# SCH_PCBproject_2024-10-10.net
KiCad netlist of a schematic drawn in EasyEDA
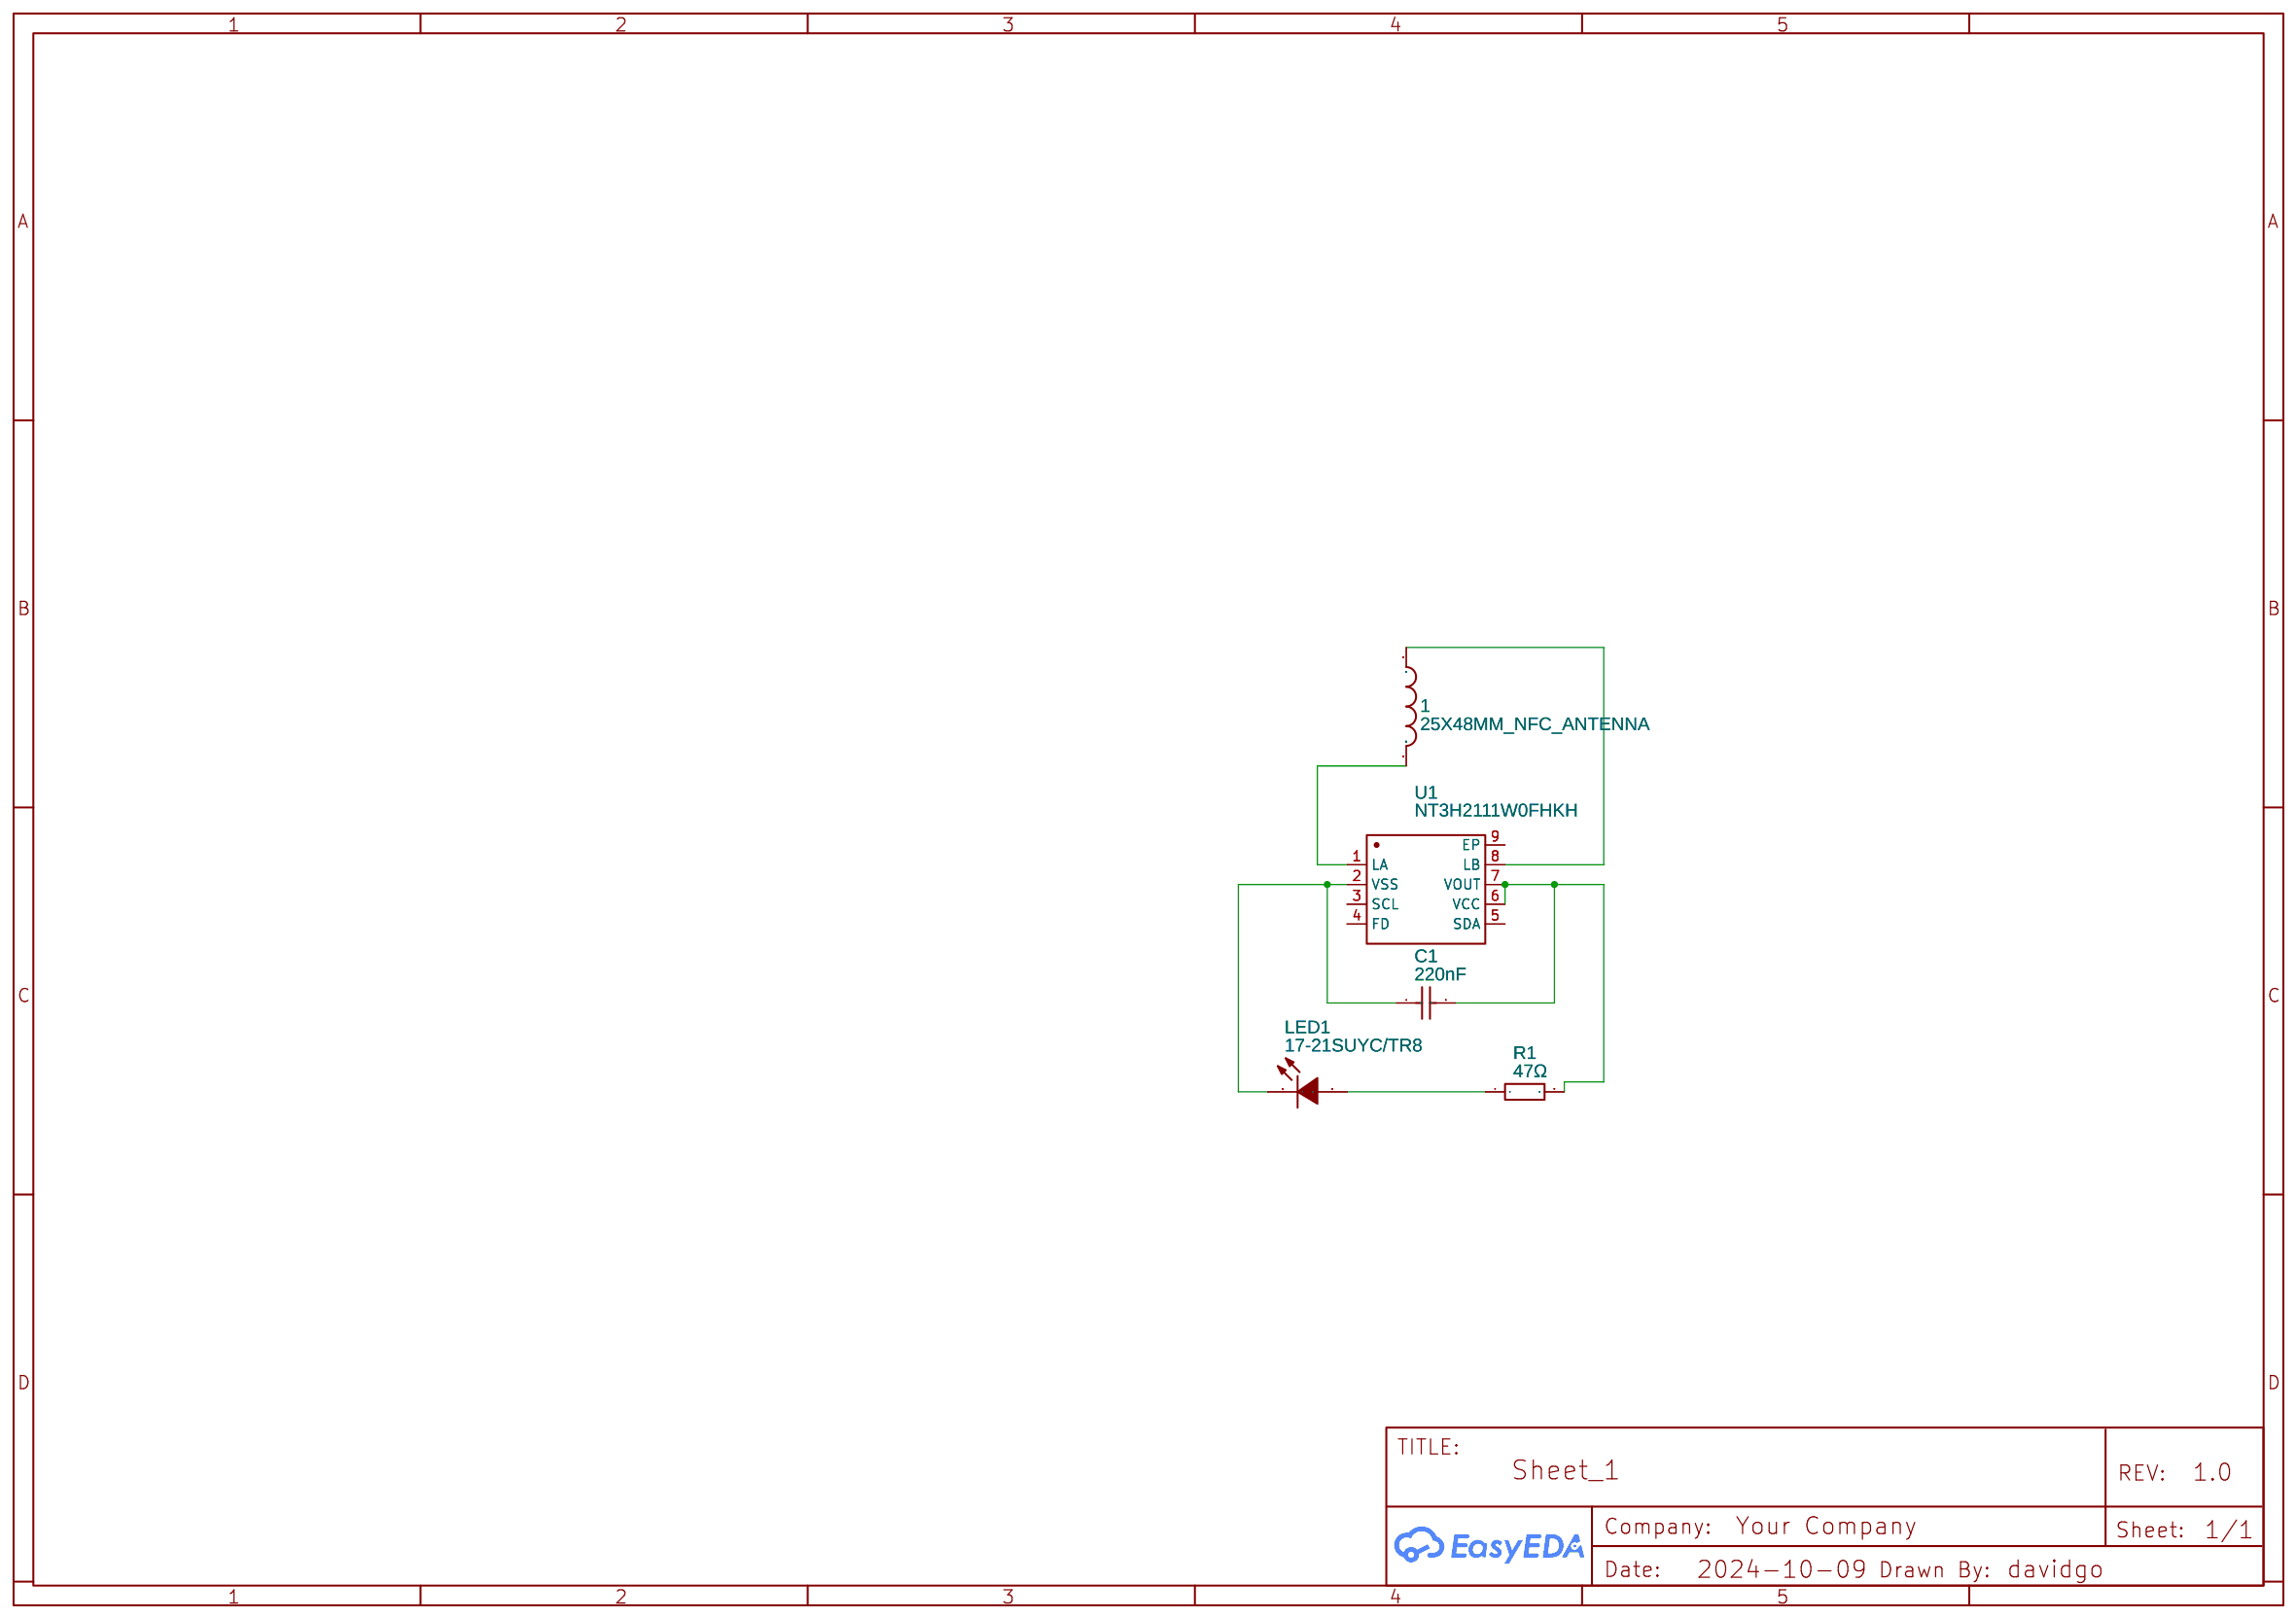
[diagram p0: schematic sheet]

(export (version "E")
  (design (tool "Eeschema 10.0.6"))
  (components
    (comp (ref "1") (value "25X48MM_NFC_ANTENNA") (libsource (lib "") (part "25X48MM_NFC_ANTENNA")))
    (comp (ref "C1")
      (value "220nF")
      (fields
        (field (name "Manufacturer Part") "CL10B224KA8NNNC")
        (field (name "Manufacturer") "SAMSUNG(三星)")
      )
      (libsource (lib "") (part "CL10B224KA8NNNC"))
    )
    (comp (ref "LED1")
      (value "17-21SUYC/TR8")
      (fields (field (name "Manufacturer Part") "KT-0805黄灯") (field (name "Manufacturer") "KENTO"))
      (libsource (lib "") (part "17-21SUYC/TR8"))
    )
    (comp (ref "R1")
      (value "47Ω")
      (fields
        (field (name "Manufacturer Part") "0603WAF470JT5E")
        (field (name "Manufacturer") "UNI-ROYAL(厚声)")
      )
      (libsource (lib "") (part "0603WAF470JT5E"))
    )
    (comp (ref "U1")
      (value "NT3H2111W0FHKH")
      (fields (field (name "Manufacturer") "NXP(恩智浦)"))
      (libsource (lib "") (part "NT3H2111W0FHKH"))
    )
  )
  (nets
    (net (code "1") (name "Net-(LED1-+)") (class "Default")
      (node (ref "LED1") (pin "1") (pinfunction "+_1") (pintype "unspecified"))
      (node (ref "R1") (pin "1") (pinfunction "1_1") (pintype "input"))
    )
    (net (code "2") (name "Net-(LED1--)") (class "Default")
      (node (ref "C1") (pin "1") (pinfunction "1_1") (pintype "input"))
      (node (ref "LED1") (pin "2") (pinfunction "-_2") (pintype "unspecified"))
      (node (ref "U1") (pin "2") (pinfunction "VSS_2") (pintype "unspecified"))
    )
    (net (code "3") (name "Net-(U1-LA)") (class "Default")
      (node (ref "1") (pin "P$2") (pinfunction "P$2_P$2") (pintype "bidirectional"))
      (node (ref "U1") (pin "1") (pinfunction "LA_1") (pintype "unspecified"))
    )
    (net (code "4") (name "Net-(U1-LB)") (class "Default")
      (node (ref "1") (pin "P$1") (pinfunction "P$1_P$1") (pintype "bidirectional"))
      (node (ref "U1") (pin "8") (pinfunction "LB_8") (pintype "unspecified"))
    )
    (net (code "5") (name "Net-(U1-VCC)") (class "Default")
      (node (ref "C1") (pin "2") (pinfunction "2_2") (pintype "input"))
      (node (ref "R1") (pin "2") (pinfunction "2_2") (pintype "input"))
      (node (ref "U1") (pin "6") (pinfunction "VCC_6") (pintype "unspecified"))
      (node (ref "U1") (pin "7") (pinfunction "VOUT_7") (pintype "unspecified"))
    )
    (net (code "6") (name "unconnected-(U1-EP-Pad9)") (class "Default")
      (node (ref "U1") (pin "9") (pinfunction "EP_9") (pintype "unspecified"))
    )
    (net (code "7") (name "unconnected-(U1-FD-Pad4)") (class "Default")
      (node (ref "U1") (pin "4") (pinfunction "FD_4") (pintype "unspecified"))
    )
    (net (code "8") (name "unconnected-(U1-SCL-Pad3)") (class "Default")
      (node (ref "U1") (pin "3") (pinfunction "SCL_3") (pintype "unspecified"))
    )
    (net (code "9") (name "unconnected-(U1-SDA-Pad5)") (class "Default")
      (node (ref "U1") (pin "5") (pinfunction "SDA_5") (pintype "unspecified"))
    )
  )
)
